# SAMV71_Xplained_Ultra_Power_Supply.net
KiCad netlist of a schematic drawn in Altium Designer
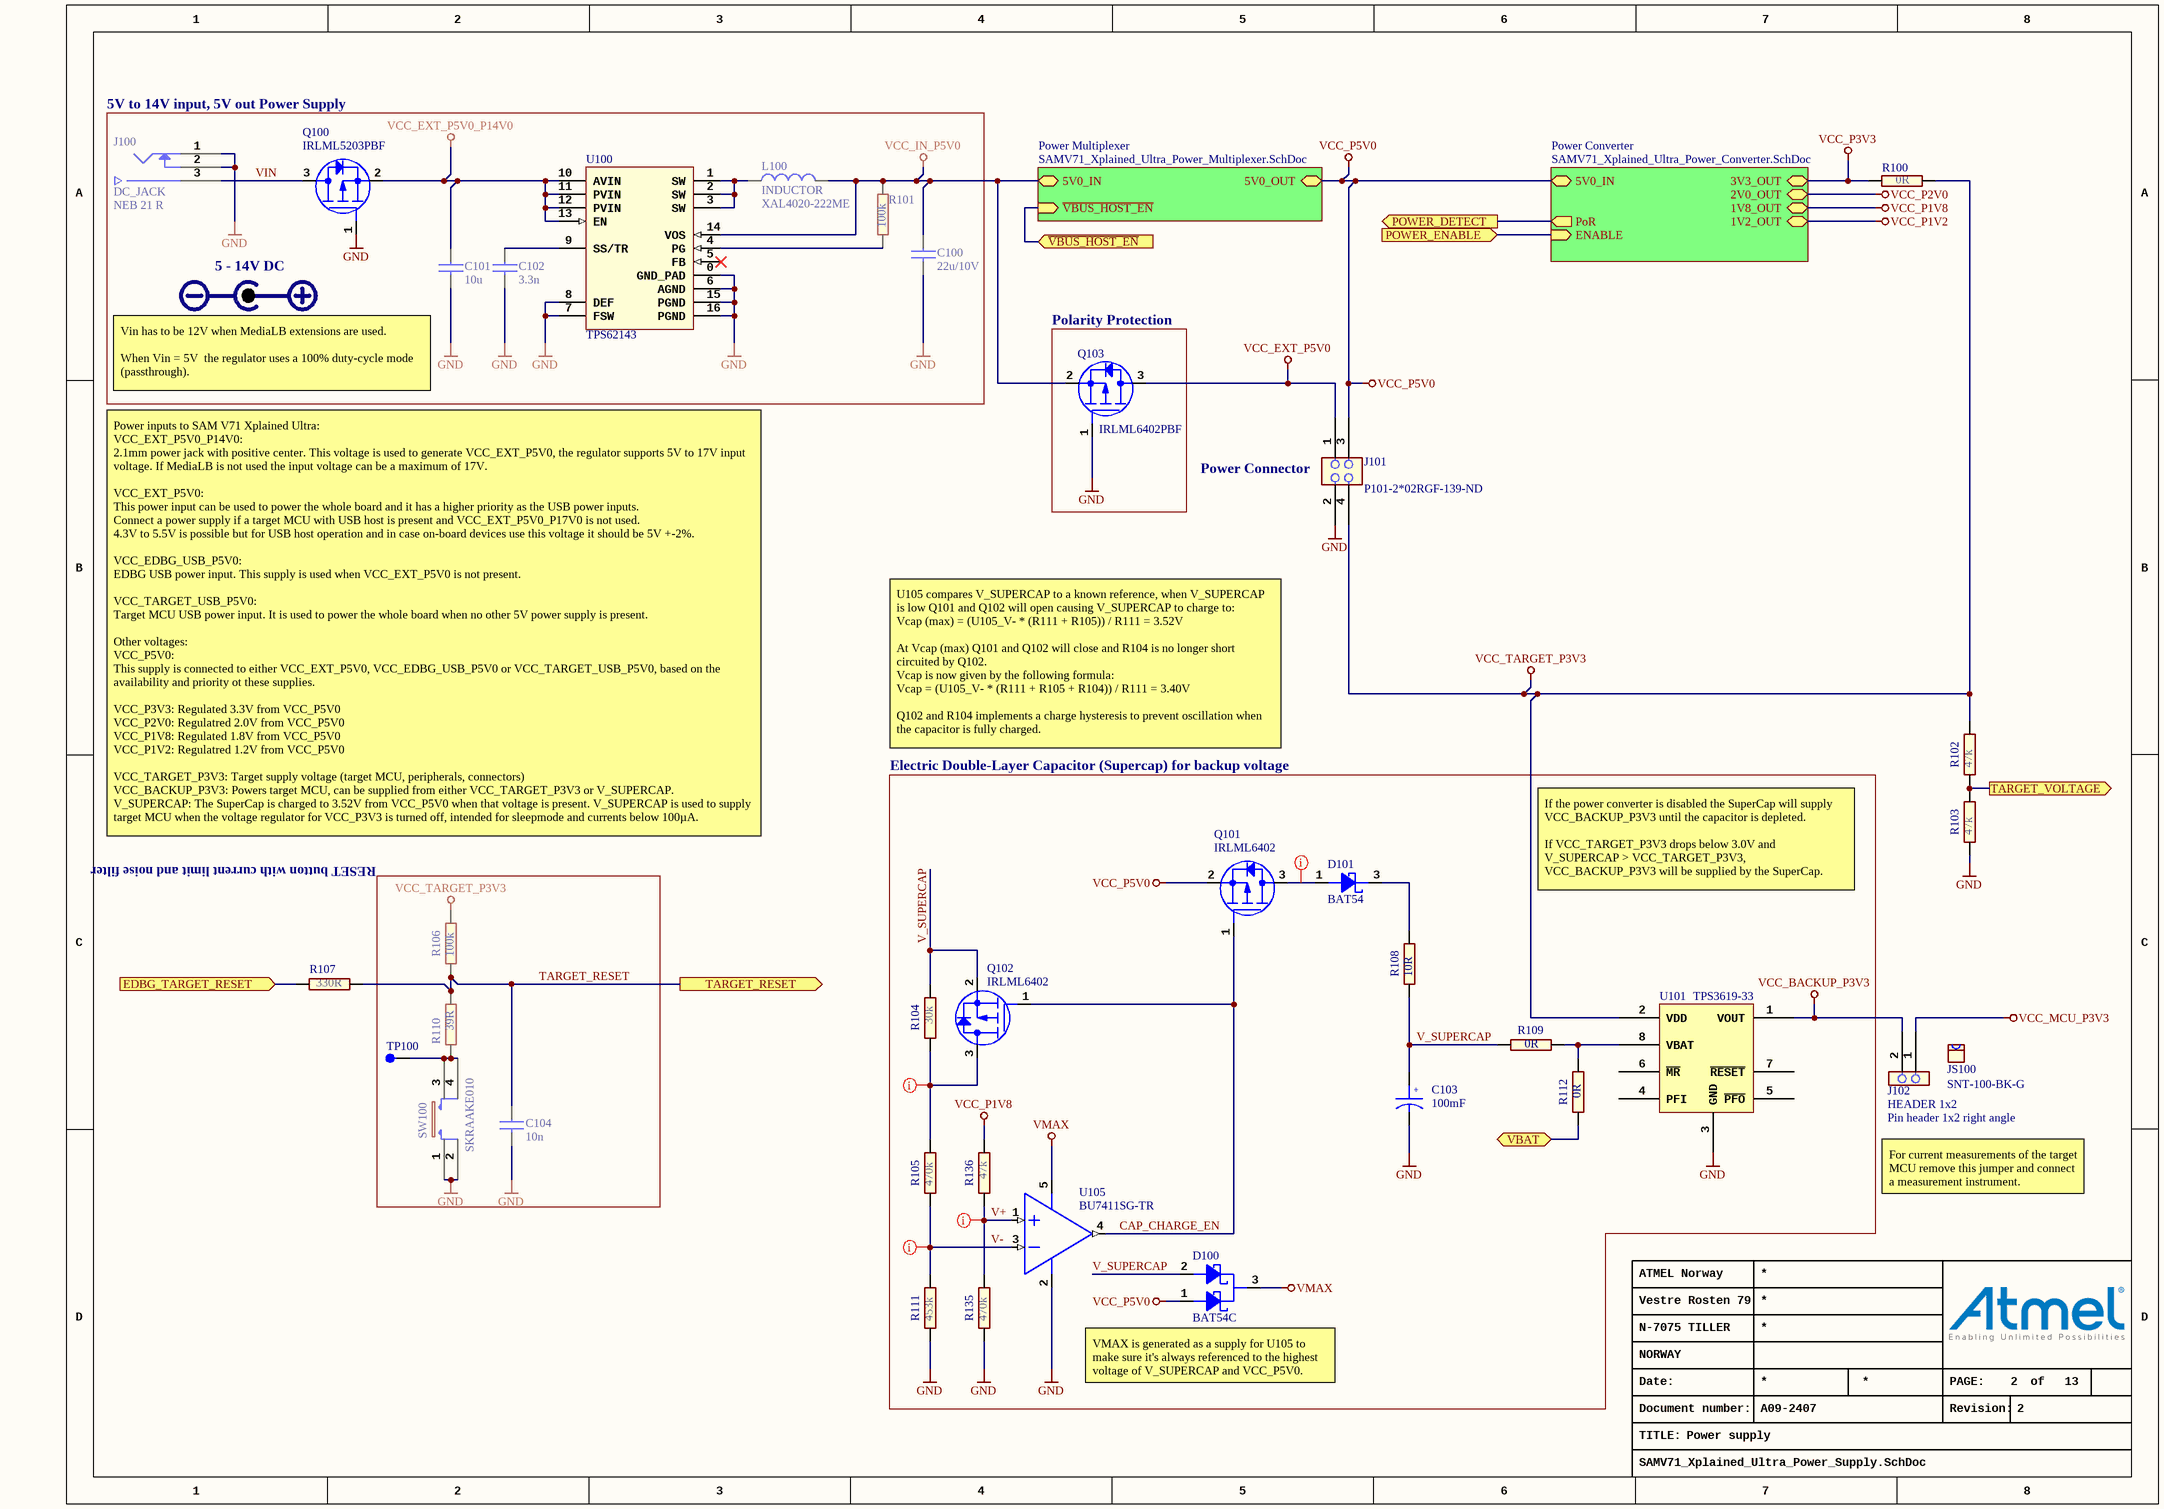
[diagram p0: SAMV71_Xplained_Ultra_Power_Supply.SchDoc]

(export (version "E")
  (design (tool "Eeschema 10.0.6"))
  (components
    (comp (ref "C100")
      (value "22u/10V")
      (footprint "AP1-00003")
      (description "Ceramic capacitor, SMD 0805, X5R, 10V, Â±20%")
      (fields (field (name "MANUFACTURER") "tdk") (field (name "MPN") "C2012X5R1A226M/0.85"))
      (libsource (lib "AltiumDbLib") (part "CAP-NONPOL"))
    )
    (comp (ref "C101")
      (value "10u")
      (footprint "AP1-00003")
      (description "Ceramic capacitor, SMD 0805, X5R, 25V, Â±10%")
      (fields (field (name "TOLERANCE") "Â±10%") (field (name "MANUFACTURER") "Murata"))
      (libsource (lib "AltiumDbLib") (part "CAP-NONPOL"))
    )
    (comp (ref "C102")
      (value "3.3n")
      (footprint "AP1-00001")
      (description "Ceramic capacitor, SMD 0402, X7R, 25V, +/-10%")
      (fields (field (name "TOLERANCE") "25V, +/-10%") (field (name "Comment") "CAP-NONPOL"))
      (libsource (lib "AltiumDbLib") (part "CAP-NONPOL"))
    )
    (comp (ref "C103")
      (value "100mF")
      (footprint "AP1-00122")
      (description "Electric Double-Layer (Supercapacitor), 100mF, SMD, 10.5mm diameter, 25Î© ESR")
      (fields (field (name "TOLERANCE") "-20/+80%") (field (name "Comment") "For reflow soldering"))
      (libsource (lib "AltiumDbLib") (part "CAP-POL"))
    )
    (comp (ref "C104")
      (value "10n")
      (footprint "AP1-00053")
      (description "Ceramic capacitor, SMD 0402, X7R, 25V, +/-10%")
      (fields (field (name "TOLERANCE") "25V, +/-10%"))
      (libsource (lib "AltiumDbLib") (part "CAP-NONPOL"))
    )
    (comp (ref "D100")
      (value "BAT54C")
      (footprint "AP5-00002")
      (description "Schottky double Diodes, NXP, SOT23-3")
      (fields (field (name "MANUFACTURER") "NXP") (field (name "Comment") "DUAL_SCHOTTKY_123"))
      (libsource (lib "AltiumDbLib") (part "DUAL_SCHOTTKY_123"))
    )
    (comp (ref "D101")
      (value "BAT54")
      (footprint "AP4-00007")
      (fields (field (name "MANUFACTURER") "Philips") (field (name "Comment") "SCHOTTKY_SMD_31"))
      (libsource (lib "AltiumDbLib") (part "SCHOTTKY_SMD_31"))
    )
    (comp (ref "J100")
      (value "DC_JACK")
      (footprint "AP8-00853")
      (description "Through hole DC jack 2.1mm, 12V, 3A")
      (fields
        (field (name "ALTIUM_VALUE") "NEB 21 R")
        (field (name "MANUFACTURER") "Lumberg")
        (field (name "MPN") "NEB 21 R")
      )
      (libsource (lib "AltiumDbLib") (part "DC_JACK"))
    )
    (comp (ref "J101")
      (value "P101-2*02RGF-139-ND")
      (footprint "AP8-00628")
      (description "Pin header, 2x2, Right Angle, 2.54mm, THT, Pin In Paste")
      (fields (field (name "Comment") "HEADER 2x2"))
      (libsource (lib "AltiumDbLib") (part "HEADER 2x2"))
    )
    (comp (ref "J102")
      (value "HEADER 1x2")
      (footprint "AP8-00367")
      (description "1x2 pin header, right angle, 2.54 mm pitch, through-hole")
      (fields
        (field (name "ALTIUM_VALUE") "Pin header 1x2 right angle")
        (field (name "MANUFACTURER") "Pro-data International Corp")
        (field (name "MPN") "2213R-2G")
      )
      (libsource (lib "AltiumDbLib") (part "HEADER 1x2"))
    )
    (comp (ref "JS100")
      (value "SNT-100-BK-G")
      (footprint "AP8-00525")
      (description "Jumper cap for 2.54mm pinheader")
      (fields (field (name "MANUFACTURER") "SAMTEC"))
      (libsource (lib "AltiumDbLib") (part "JUMPER_CAP"))
    )
    (comp (ref "L100")
      (value "INDUCTOR")
      (footprint "AP3-00119")
      (description "2.2ÂµH Shielded Power Inductor, 4x4x2mm, Isat=5.6A , Irms=4.0A , DCR=35.2mÎ©")
      (fields (field (name "ALTIUM_VALUE") "XAL4020-222ME") (field (name "TOLERANCE") "20%"))
      (libsource (lib "AltiumDbLib") (part "INDUCTOR"))
    )
    (comp (ref "Q100")
      (value "IRLML5203PBF")
      (footprint "AP5-00002")
      (fields (field (name "MANUFACTURER") "International Rectifier") (field (name "Comment") "MOSFET_P_GSD"))
      (libsource (lib "AltiumDbLib") (part "MOSFET_P_GSD"))
    )
    (comp (ref "Q101")
      (value "IRLML6402")
      (footprint "AP5-00002")
      (description "P-ch. MOSFET. -30V, -3.7A continuous,RDS(ON)=0.05Ohm@VGS=-4,5V, RDS(ON)=0.08Ohm@VGS=-2.5V")
      (fields (field (name "MANUFACTURER") "International Rectifier") (field (name "MPN") "IRLML6402PBF"))
      (libsource (lib "AltiumDbLib") (part "MOSFET_P_GSD"))
    )
    (comp (ref "Q102")
      (value "IRLML6402")
      (footprint "AP5-00002")
      (description "P-ch. MOSFET. -30V, -3.7A continuous,RDS(ON)=0.05Ohm@VGS=-4,5V, RDS(ON)=0.08Ohm@VGS=-2.5V")
      (fields (field (name "MANUFACTURER") "International Rectifier") (field (name "MPN") "IRLML6402PBF"))
      (libsource (lib "AltiumDbLib") (part "MOSFET_P_GSD"))
    )
    (comp (ref "Q103")
      (value "IRLML6402PBF")
      (footprint "AP5-00002")
      (description "P-ch. MOSFET. -30V, -3.7A continuous,RDS(ON)=0.05Ohm@VGS=-4,5V, RDS(ON)=0.08Ohm@VGS=-2.5V")
      (fields (field (name "MANUFACTURER") "International Rectifier") (field (name "Comment") "MOSFET_P_GSD"))
      (libsource (lib "AltiumDbLib") (part "MOSFET_P_GSD"))
    )
    (comp (ref "R100")
      (value "0R")
      (footprint "AP2-00000")
      (description "Thick film resistor, SMD 0402, 1/16W, 1%")
      (fields (field (name "TOLERANCE") "1 %") (field (name "Comment") "R2"))
      (libsource (lib "") (part "R2_3"))
    )
    (comp (ref "R101")
      (value "100k")
      (footprint "AP2-00000")
      (description "Thick film resistor, SMD 0402, 1/16W, 1%")
      (fields (field (name "TOLERANCE") "1 %") (field (name "Comment") "R2"))
      (libsource (lib "") (part "R2_1"))
    )
    (comp (ref "R102")
      (value "47k")
      (footprint "AP2-00000")
      (description "Thick film resistor, SMD 0402, 1/16W, 1%")
      (fields (field (name "TOLERANCE") "1 %") (field (name "Comment") "R2"))
      (libsource (lib "AltiumDbLib") (part "R2"))
    )
    (comp (ref "R103")
      (value "47k")
      (footprint "AP2-00000")
      (description "Thick film resistor, SMD 0402, 1/16W, 1%")
      (fields (field (name "TOLERANCE") "1 %") (field (name "Comment") "R2"))
      (libsource (lib "AltiumDbLib") (part "R2"))
    )
    (comp (ref "R104")
      (value "30k")
      (footprint "AP2-00000")
      (description "Thick film resistor, SMD 0402, 1/16W, 1%")
      (fields (field (name "TOLERANCE") "1 %") (field (name "Comment") "R2"))
      (libsource (lib "") (part "R2_2"))
    )
    (comp (ref "R105")
      (value "470k")
      (footprint "AP2-00000")
      (description "Thick film resistor, SMD 0402, 1/16W, 1%")
      (fields (field (name "TOLERANCE") "1 %") (field (name "Comment") "R2"))
      (libsource (lib "") (part "R2_2"))
    )
    (comp (ref "R106")
      (value "100k")
      (footprint "AP2-00011")
      (description "Thick film resistor, SMD 0402, 1/16W, 1%")
      (fields (field (name "TOLERANCE") "1 %") (field (name "Comment") "R2"))
      (libsource (lib "") (part "R2_2"))
    )
    (comp (ref "R107")
      (value "330R")
      (footprint "AP2-00011")
      (description "Thick film resistor, SMD 0402, 1/16W, 1%")
      (fields (field (name "TOLERANCE") "1 %") (field (name "Comment") "R2"))
      (libsource (lib "") (part "R2_3"))
    )
    (comp (ref "R108")
      (value "10R")
      (footprint "AP2-00000")
      (description "Thick film resistor, SMD 0402, 1/16W, 1%")
      (fields (field (name "TOLERANCE") "1 %") (field (name "Comment") "R2"))
      (libsource (lib "") (part "R2_1"))
    )
    (comp (ref "R109")
      (value "0R")
      (footprint "AP2-00000")
      (description "RES 0.0 OHM 1/16W 0402 SMD")
      (fields (field (name "TOLERANCE") "1 %") (field (name "MANUFACTURER") "(n/a)"))
      (libsource (lib "") (part "R2_3"))
    )
    (comp (ref "R110")
      (value "39R")
      (footprint "AP2-00011")
      (description "Thick film resistor, SMD 0402, 1/16W, 1%")
      (fields (field (name "TOLERANCE") "1 %") (field (name "Comment") "R2"))
      (libsource (lib "") (part "R2_4"))
    )
    (comp (ref "R111")
      (value "453k")
      (footprint "AP2-00000")
      (description "Thick film resistor, SMD 0402, 1/16W, 1%")
      (fields (field (name "TOLERANCE") "1 %") (field (name "Comment") "R2"))
      (libsource (lib "") (part "R2_2"))
    )
    (comp (ref "R112")
      (value "0R")
      (footprint "AP2-00000")
      (description "RES 0.0 OHM 1/16W 0402 SMD")
      (fields (field (name "TOLERANCE") "1 %") (field (name "MANUFACTURER") "(n/a)"))
      (libsource (lib "") (part "R2_2"))
    )
    (comp (ref "R135")
      (value "470k")
      (footprint "AP2-00000")
      (description "Thick film resistor, SMD 0402, 1/16W, 1%")
      (fields (field (name "TOLERANCE") "1 %") (field (name "Comment") "R2"))
      (libsource (lib "") (part "R2_2"))
    )
    (comp (ref "R136")
      (value "47k")
      (footprint "AP2-00000")
      (description "Thick film resistor, SMD 0402, 1/16W, 1%")
      (fields (field (name "TOLERANCE") "1 %") (field (name "Comment") "?"))
      (libsource (lib "") (part "R2_2"))
    )
    (comp (ref "SW100")
      (value "SKRAAKE010")
      (footprint "AP8-00137")
      (description "6.2x6.2 mm SMD tact switch, same as A08-0091 but less force is needed")
      (fields
        (field (name "MANUFACTURER") "ALPS")
        (field (name "Comment") "Can be ordered in low volumes from Mouser")
      )
      (libsource (lib "AltiumDbLib") (part "PUSHBUTTON1"))
    )
    (comp (ref "TP100")
      (value "TESTPOINT")
      (footprint "AP8-00010")
      (description "Single SMD testpad")
      (libsource (lib "AltiumDbLib") (part "TESTPOINT"))
    )
    (comp (ref "U100")
      (value "TPS62143")
      (footprint "AP6-00313")
      (description "5V to 17V in, 5V 2A out, Step-Down Converter")
      (fields
        (field (name "Comment") "100% duty-cycle mode, supports input voltage close to 5V with 5V output!")
      )
      (libsource (lib "AltiumDbLib") (part "TPS62143"))
    )
    (comp (ref "U101")
      (value "TPS3619-33")
      (footprint "AP6-00382")
      (description "Backup battery supervisors for RAM retention")
      (fields (field (name "MANUFACTURER") "Texas Instruments") (field (name "MPN") "TPS3619-33DGK"))
      (libsource (lib "AltiumDbLib") (part "TPS3619"))
    )
    (comp (ref "U105")
      (value "BU7411SG-TR")
      (footprint "AP6-00087")
      (description "Single, Low Voltage (1.6-5.5V), Low Power (0.35ÂµA), low cost")
      (libsource (lib "AltiumDbLib") (part "LMV321M5"))
    )
  )
  (nets
    (net (code "1") (name "/CAP_CHARGE_EN") (class "Default")
      (node (ref "Q101") (pin "1") (pinfunction "G_1") (pintype "passive"))
      (node (ref "Q102") (pin "1") (pinfunction "G_1") (pintype "passive"))
      (node (ref "U105") (pin "4") (pinfunction "OUT_4") (pintype "output"))
    )
    (net (code "2") (name "/EDBG_TARGET_RESET") (class "Default")
      (node (ref "R107") (pin "1") (pinfunction "1_1") (pintype "passive"))
    )
    (net (code "5") (name "/TARGET_RESET") (class "Default")
      (node (ref "C104") (pin "1") (pinfunction "1_1") (pintype "passive"))
      (node (ref "R106") (pin "1") (pinfunction "1_1") (pintype "passive"))
      (node (ref "R107") (pin "2") (pinfunction "2_2") (pintype "passive"))
      (node (ref "R110") (pin "2") (pinfunction "2_2") (pintype "passive"))
    )
    (net (code "6") (name "/TARGET_VOLTAGE") (class "Default")
      (node (ref "R102") (pin "1") (pinfunction "1_1") (pintype "passive"))
      (node (ref "R103") (pin "2") (pinfunction "2_2") (pintype "passive"))
    )
    (net (code "7") (name "/V+") (class "Default")
      (node (ref "R135") (pin "2") (pinfunction "2_2") (pintype "passive"))
      (node (ref "R136") (pin "1") (pinfunction "1_1") (pintype "passive"))
      (node (ref "U105") (pin "1") (pinfunction "IN+_1") (pintype "input"))
    )
    (net (code "8") (name "/V-") (class "Default")
      (node (ref "R105") (pin "1") (pinfunction "1_1") (pintype "passive"))
      (node (ref "R111") (pin "2") (pinfunction "2_2") (pintype "passive"))
      (node (ref "U105") (pin "3") (pinfunction "IN-_3") (pintype "input"))
    )
    (net (code "9") (name "/VBAT") (class "Default")
      (node (ref "R112") (pin "1") (pinfunction "1_1") (pintype "passive"))
    )
    (net (code "10") (name "/VIN") (class "Default")
      (node (ref "J100") (pin "3") (pinfunction "3_3") (pintype "passive"))
      (node (ref "Q100") (pin "3") (pinfunction "D_3") (pintype "passive"))
    )
    (net (code "11") (name "/V_SUPERCAP") (class "Default")
      (node (ref "C103") (pin "1") (pinfunction "1_1") (pintype "passive"))
      (node (ref "D100") (pin "2") (pinfunction "ANODE2_2") (pintype "passive"))
      (node (ref "Q102") (pin "2") (pinfunction "S_2") (pintype "passive"))
      (node (ref "R104") (pin "2") (pinfunction "2_2") (pintype "passive"))
      (node (ref "R108") (pin "2") (pinfunction "2_2") (pintype "passive"))
      (node (ref "R109") (pin "1") (pinfunction "1_1") (pintype "passive"))
    )
    (net (code "13") (name "GND") (class "Default")
      (node (ref "C100") (pin "2") (pinfunction "2_2") (pintype "passive"))
      (node (ref "C101") (pin "2") (pinfunction "2_2") (pintype "passive"))
      (node (ref "C102") (pin "2") (pinfunction "2_2") (pintype "passive"))
      (node (ref "C103") (pin "2") (pinfunction "2_2") (pintype "passive"))
      (node (ref "C104") (pin "2") (pinfunction "2_2") (pintype "passive"))
      (node (ref "J100") (pin "1") (pinfunction "1_1") (pintype "passive"))
      (node (ref "J100") (pin "2") (pinfunction "2_2") (pintype "passive"))
      (node (ref "J101") (pin "2") (pinfunction "2_2") (pintype "passive"))
      (node (ref "Q100") (pin "1") (pinfunction "G_1") (pintype "passive"))
      (node (ref "Q103") (pin "1") (pinfunction "G_1") (pintype "passive"))
      (node (ref "R103") (pin "1") (pinfunction "1_1") (pintype "passive"))
      (node (ref "R111") (pin "1") (pinfunction "1_1") (pintype "passive"))
      (node (ref "R135") (pin "1") (pinfunction "1_1") (pintype "passive"))
      (node (ref "SW100") (pin "1") (pinfunction "1_1") (pintype "passive"))
      (node (ref "SW100") (pin "2") (pinfunction "2_2") (pintype "passive"))
      (node (ref "U100") (pin "0") (pinfunction "GND_PAD_0") (pintype "passive"))
      (node (ref "U100") (pin "15") (pinfunction "PGND_15") (pintype "power_in"))
      (node (ref "U100") (pin "16") (pinfunction "PGND_16") (pintype "power_in"))
      (node (ref "U100") (pin "6") (pinfunction "AGND_6") (pintype "power_in"))
      (node (ref "U100") (pin "7") (pinfunction "FSW_7") (pintype "power_in"))
      (node (ref "U100") (pin "8") (pinfunction "DEF_8") (pintype "power_in"))
      (node (ref "U101") (pin "3") (pinfunction "GND_3") (pintype "passive"))
      (node (ref "U105") (pin "2") (pinfunction "GND_2") (pintype "power_in"))
    )
    (net (code "14") (name "Net-(D101-ANODE)") (class "Default")
      (node (ref "D101") (pin "1") (pinfunction "ANODE_1") (pintype "passive"))
      (node (ref "Q101") (pin "3") (pinfunction "D_3") (pintype "passive"))
    )
    (net (code "15") (name "Net-(D101-CATHODE)") (class "Default")
      (node (ref "D101") (pin "3") (pinfunction "CATHODE_3") (pintype "passive"))
      (node (ref "R108") (pin "1") (pinfunction "1_1") (pintype "passive"))
    )
    (net (code "16") (name "Net-(L100-Pad1)") (class "Default")
      (node (ref "L100") (pin "1") (pinfunction "1_1") (pintype "passive"))
      (node (ref "U100") (pin "1") (pinfunction "SW_1") (pintype "power_in"))
      (node (ref "U100") (pin "2") (pinfunction "SW_2") (pintype "power_in"))
      (node (ref "U100") (pin "3") (pinfunction "SW_3") (pintype "power_in"))
    )
    (net (code "17") (name "Net-(Q102-D)") (class "Default")
      (node (ref "Q102") (pin "3") (pinfunction "D_3") (pintype "passive"))
      (node (ref "R104") (pin "1") (pinfunction "1_1") (pintype "passive"))
      (node (ref "R105") (pin "2") (pinfunction "2_2") (pintype "passive"))
    )
    (net (code "18") (name "Net-(R110-Pad1)") (class "Default")
      (node (ref "R110") (pin "1") (pinfunction "1_1") (pintype "passive"))
      (node (ref "SW100") (pin "3") (pinfunction "3_3") (pintype "passive"))
      (node (ref "SW100") (pin "4") (pinfunction "4_4") (pintype "passive"))
      (node (ref "TP100") (pin "1") (pinfunction "1_1") (pintype "passive"))
    )
    (net (code "19") (name "Net-(U100-PG)") (class "Default")
      (node (ref "R101") (pin "2") (pinfunction "2_2") (pintype "passive"))
      (node (ref "U100") (pin "4") (pinfunction "PG_4") (pintype "input"))
    )
    (net (code "20") (name "Net-(U100-SS{slash}TR)") (class "Default")
      (node (ref "C102") (pin "1") (pinfunction "1_1") (pintype "passive"))
      (node (ref "U100") (pin "9") (pinfunction "SS/TR_9") (pintype "passive"))
    )
    (net (code "21") (name "Net-(U101-VBAT)") (class "Default")
      (node (ref "R109") (pin "2") (pinfunction "2_2") (pintype "passive"))
      (node (ref "R112") (pin "2") (pinfunction "2_2") (pintype "passive"))
      (node (ref "U101") (pin "8") (pinfunction "VBAT_8") (pintype "passive"))
    )
    (net (code "22") (name "VCC_BACKUP_P3V3") (class "Default")
      (node (ref "J102") (pin "2") (pinfunction "2_2") (pintype "passive"))
      (node (ref "U101") (pin "1") (pinfunction "VOUT_1") (pintype "passive"))
    )
    (net (code "23") (name "VCC_EXT_P5V0") (class "Default")
      (node (ref "J101") (pin "1") (pinfunction "1_1") (pintype "passive"))
      (node (ref "Q103") (pin "3") (pinfunction "D_3") (pintype "passive"))
    )
    (net (code "24") (name "VCC_EXT_P5V0_P14V0") (class "Default")
      (node (ref "C101") (pin "1") (pinfunction "1_1") (pintype "passive"))
      (node (ref "Q100") (pin "2") (pinfunction "S_2") (pintype "passive"))
      (node (ref "U100") (pin "10") (pinfunction "AVIN_10") (pintype "power_in"))
      (node (ref "U100") (pin "11") (pinfunction "PVIN_11") (pintype "power_in"))
      (node (ref "U100") (pin "12") (pinfunction "PVIN_12") (pintype "power_in"))
      (node (ref "U100") (pin "13") (pinfunction "EN_13") (pintype "input"))
    )
    (net (code "25") (name "VCC_IN_P5V0") (class "Default")
      (node (ref "C100") (pin "1") (pinfunction "1_1") (pintype "passive"))
      (node (ref "L100") (pin "2") (pinfunction "2_2") (pintype "passive"))
      (node (ref "Q103") (pin "2") (pinfunction "S_2") (pintype "passive"))
      (node (ref "R101") (pin "1") (pinfunction "1_1") (pintype "passive"))
      (node (ref "U100") (pin "14") (pinfunction "VOS_14") (pintype "input"))
    )
    (net (code "26") (name "VCC_MCU_P3V3") (class "Default")
      (node (ref "J102") (pin "1") (pinfunction "1_1") (pintype "passive"))
    )
    (net (code "28") (name "VCC_P1V8") (class "Default")
      (node (ref "R136") (pin "2") (pinfunction "2_2") (pintype "passive"))
    )
    (net (code "30") (name "VCC_P3V3") (class "Default")
      (node (ref "R100") (pin "1") (pinfunction "1_1") (pintype "passive"))
    )
    (net (code "31") (name "VCC_P5V0") (class "Default")
      (node (ref "D100") (pin "1") (pinfunction "ANODE1_1") (pintype "passive"))
      (node (ref "J101") (pin "3") (pinfunction "3_3") (pintype "passive"))
      (node (ref "Q101") (pin "2") (pinfunction "S_2") (pintype "passive"))
    )
    (net (code "32") (name "VCC_TARGET_P3V3") (class "Default")
      (node (ref "J101") (pin "4") (pinfunction "4_4") (pintype "passive"))
      (node (ref "R100") (pin "2") (pinfunction "2_2") (pintype "passive"))
      (node (ref "R102") (pin "2") (pinfunction "2_2") (pintype "passive"))
      (node (ref "R106") (pin "2") (pinfunction "2_2") (pintype "passive"))
      (node (ref "U101") (pin "2") (pinfunction "VDD_2") (pintype "passive"))
    )
    (net (code "33") (name "VMAX") (class "Default")
      (node (ref "D100") (pin "3") (pinfunction "CATHODE_3") (pintype "passive"))
      (node (ref "U105") (pin "5") (pinfunction "VCC_5") (pintype "power_in"))
    )
    (net (code "34") (name "unconnected-(U100-FB-Pad5)") (class "Default")
      (node (ref "U100") (pin "5") (pinfunction "FB_5") (pintype "input+no_connect"))
    )
    (net (code "35") (name "unconnected-(U101-PFI-Pad4)") (class "Default")
      (node (ref "U101") (pin "4") (pinfunction "PFI_4") (pintype "passive"))
    )
    (net (code "36") (name "unconnected-(U101-~{MR}-Pad6)") (class "Default")
      (node (ref "U101") (pin "6") (pinfunction "~{MR}_6") (pintype "passive"))
    )
    (net (code "37") (name "unconnected-(U101-~{PFO}-Pad5)") (class "Default")
      (node (ref "U101") (pin "5") (pinfunction "~{PFO}_5") (pintype "passive"))
    )
    (net (code "38") (name "unconnected-(U101-~{RESET}-Pad7)") (class "Default")
      (node (ref "U101") (pin "7") (pinfunction "~{RESET}_7") (pintype "passive"))
    )
  )
)
